# Sheet1.net
KiCad netlist of a schematic drawn in Altium Designer
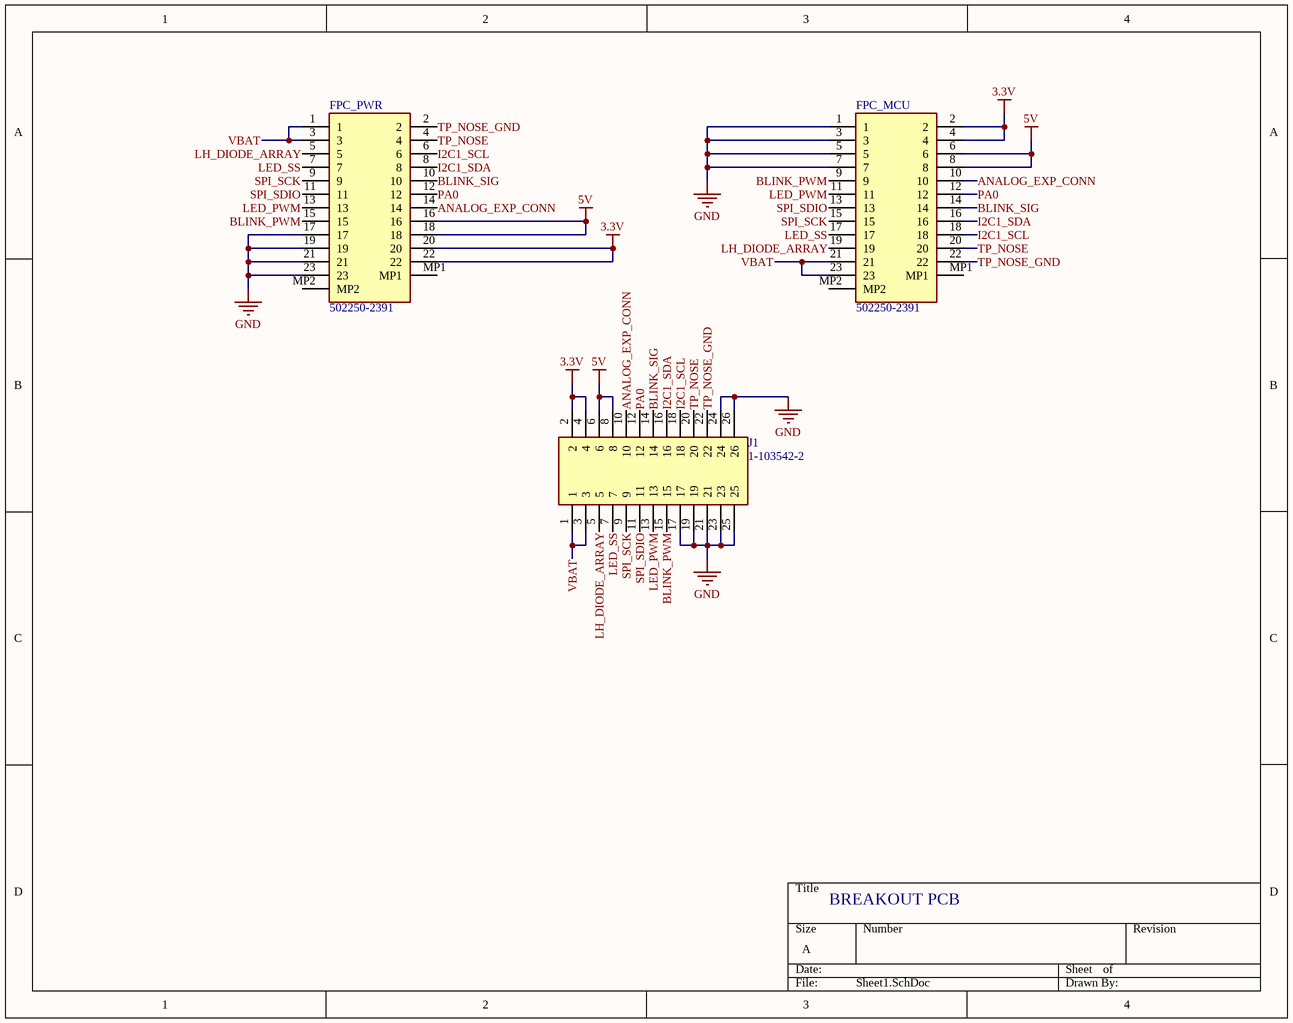
[diagram p0: Sheet1.SchDoc]

(export (version "E")
  (design (tool "Eeschema 10.0.6"))
  (components
    (comp (ref "FPC_MCU")
      (value "502250-2391")
      (footprint "SamacSys:5022502391")
      (description "Connector")
      (fields (field (name "MOUSER PART NUMBER") "538-502250-2391"))
      (libsource (lib "*") (part "502250-2391"))
    )
    (comp (ref "FPC_PWR")
      (value "502250-2391")
      (footprint "SamacSys:5022502391")
      (description "Connector")
      (fields (field (name "MOUSER PART NUMBER") "538-502250-2391"))
      (libsource (lib "*") (part "502250-2391"))
    )
    (comp (ref "J1")
      (value "1-103542-2")
      (footprint "SamacSys:HDRV26W89P254X254_2X13_3261X506X1074P")
      (description "Connector")
      (fields (field (name "MOUSER PART NUMBER") "571-1-103542-2"))
      (libsource (lib "*") (part "1-103542-2"))
    )
  )
  (nets
    (net (code "1") (name "/ANALOG_EXP_CONN") (class "Default")
      (node (ref "FPC_MCU") (pin "10") (pinfunction "10_10") (pintype "passive"))
      (node (ref "FPC_PWR") (pin "14") (pinfunction "14_14") (pintype "passive"))
      (node (ref "J1") (pin "10") (pinfunction "10_10") (pintype "passive"))
    )
    (net (code "2") (name "/BLINK_PWM") (class "Default")
      (node (ref "FPC_MCU") (pin "9") (pinfunction "9_9") (pintype "passive"))
      (node (ref "FPC_PWR") (pin "15") (pinfunction "15_15") (pintype "passive"))
      (node (ref "J1") (pin "15") (pinfunction "15_15") (pintype "passive"))
    )
    (net (code "3") (name "/BLINK_SIG") (class "Default")
      (node (ref "FPC_MCU") (pin "14") (pinfunction "14_14") (pintype "passive"))
      (node (ref "FPC_PWR") (pin "10") (pinfunction "10_10") (pintype "passive"))
      (node (ref "J1") (pin "14") (pinfunction "14_14") (pintype "passive"))
    )
    (net (code "4") (name "/I2C1_SCL") (class "Default")
      (node (ref "FPC_MCU") (pin "18") (pinfunction "18_18") (pintype "passive"))
      (node (ref "FPC_PWR") (pin "6") (pinfunction "6_6") (pintype "passive"))
      (node (ref "J1") (pin "18") (pinfunction "18_18") (pintype "passive"))
    )
    (net (code "5") (name "/I2C1_SDA") (class "Default")
      (node (ref "FPC_MCU") (pin "16") (pinfunction "16_16") (pintype "passive"))
      (node (ref "FPC_PWR") (pin "8") (pinfunction "8_8") (pintype "passive"))
      (node (ref "J1") (pin "16") (pinfunction "16_16") (pintype "passive"))
    )
    (net (code "6") (name "/LED_PWM") (class "Default")
      (node (ref "FPC_MCU") (pin "11") (pinfunction "11_11") (pintype "passive"))
      (node (ref "FPC_PWR") (pin "13") (pinfunction "13_13") (pintype "passive"))
      (node (ref "J1") (pin "13") (pinfunction "13_13") (pintype "passive"))
    )
    (net (code "7") (name "/LED_SS") (class "Default")
      (node (ref "FPC_MCU") (pin "17") (pinfunction "17_17") (pintype "passive"))
      (node (ref "FPC_PWR") (pin "7") (pinfunction "7_7") (pintype "passive"))
      (node (ref "J1") (pin "7") (pinfunction "7_7") (pintype "passive"))
    )
    (net (code "8") (name "/LH_DIODE_ARRAY") (class "Default")
      (node (ref "FPC_MCU") (pin "19") (pinfunction "19_19") (pintype "passive"))
      (node (ref "FPC_PWR") (pin "5") (pinfunction "5_5") (pintype "passive"))
      (node (ref "J1") (pin "5") (pinfunction "5_5") (pintype "passive"))
    )
    (net (code "9") (name "/PA0") (class "Default")
      (node (ref "FPC_MCU") (pin "12") (pinfunction "12_12") (pintype "passive"))
      (node (ref "FPC_PWR") (pin "12") (pinfunction "12_12") (pintype "passive"))
      (node (ref "J1") (pin "12") (pinfunction "12_12") (pintype "passive"))
    )
    (net (code "10") (name "/SPI_SCK") (class "Default")
      (node (ref "FPC_MCU") (pin "15") (pinfunction "15_15") (pintype "passive"))
      (node (ref "FPC_PWR") (pin "9") (pinfunction "9_9") (pintype "passive"))
      (node (ref "J1") (pin "9") (pinfunction "9_9") (pintype "passive"))
    )
    (net (code "11") (name "/SPI_SDIO") (class "Default")
      (node (ref "FPC_MCU") (pin "13") (pinfunction "13_13") (pintype "passive"))
      (node (ref "FPC_PWR") (pin "11") (pinfunction "11_11") (pintype "passive"))
      (node (ref "J1") (pin "11") (pinfunction "11_11") (pintype "passive"))
    )
    (net (code "12") (name "/TP_NOSE") (class "Default")
      (node (ref "FPC_MCU") (pin "20") (pinfunction "20_20") (pintype "passive"))
      (node (ref "FPC_PWR") (pin "4") (pinfunction "4_4") (pintype "passive"))
      (node (ref "J1") (pin "20") (pinfunction "20_20") (pintype "passive"))
    )
    (net (code "13") (name "/TP_NOSE_GND") (class "Default")
      (node (ref "FPC_MCU") (pin "22") (pinfunction "22_22") (pintype "passive"))
      (node (ref "FPC_PWR") (pin "2") (pinfunction "2_2") (pintype "passive"))
      (node (ref "J1") (pin "22") (pinfunction "22_22") (pintype "passive"))
    )
    (net (code "14") (name "/VBAT") (class "Default")
      (node (ref "FPC_MCU") (pin "21") (pinfunction "21_21") (pintype "passive"))
      (node (ref "FPC_MCU") (pin "23") (pinfunction "23_23") (pintype "passive"))
      (node (ref "FPC_PWR") (pin "1") (pinfunction "1_1") (pintype "passive"))
      (node (ref "FPC_PWR") (pin "3") (pinfunction "3_3") (pintype "passive"))
      (node (ref "J1") (pin "1") (pinfunction "1_1") (pintype "passive"))
      (node (ref "J1") (pin "3") (pinfunction "3_3") (pintype "passive"))
    )
    (net (code "15") (name "3.3V") (class "Default")
      (node (ref "FPC_MCU") (pin "2") (pinfunction "2_2") (pintype "passive"))
      (node (ref "FPC_MCU") (pin "4") (pinfunction "4_4") (pintype "passive"))
      (node (ref "FPC_PWR") (pin "20") (pinfunction "20_20") (pintype "passive"))
      (node (ref "FPC_PWR") (pin "22") (pinfunction "22_22") (pintype "passive"))
      (node (ref "J1") (pin "2") (pinfunction "2_2") (pintype "passive"))
      (node (ref "J1") (pin "4") (pinfunction "4_4") (pintype "passive"))
    )
    (net (code "16") (name "5V") (class "Default")
      (node (ref "FPC_MCU") (pin "6") (pinfunction "6_6") (pintype "passive"))
      (node (ref "FPC_MCU") (pin "8") (pinfunction "8_8") (pintype "passive"))
      (node (ref "FPC_PWR") (pin "16") (pinfunction "16_16") (pintype "passive"))
      (node (ref "FPC_PWR") (pin "18") (pinfunction "18_18") (pintype "passive"))
      (node (ref "J1") (pin "6") (pinfunction "6_6") (pintype "passive"))
      (node (ref "J1") (pin "8") (pinfunction "8_8") (pintype "passive"))
    )
    (net (code "17") (name "GND") (class "Default")
      (node (ref "FPC_MCU") (pin "1") (pinfunction "1_1") (pintype "passive"))
      (node (ref "FPC_MCU") (pin "3") (pinfunction "3_3") (pintype "passive"))
      (node (ref "FPC_MCU") (pin "5") (pinfunction "5_5") (pintype "passive"))
      (node (ref "FPC_MCU") (pin "7") (pinfunction "7_7") (pintype "passive"))
      (node (ref "FPC_PWR") (pin "17") (pinfunction "17_17") (pintype "passive"))
      (node (ref "FPC_PWR") (pin "19") (pinfunction "19_19") (pintype "passive"))
      (node (ref "FPC_PWR") (pin "21") (pinfunction "21_21") (pintype "passive"))
      (node (ref "FPC_PWR") (pin "23") (pinfunction "23_23") (pintype "passive"))
      (node (ref "J1") (pin "17") (pinfunction "17_17") (pintype "passive"))
      (node (ref "J1") (pin "19") (pinfunction "19_19") (pintype "passive"))
      (node (ref "J1") (pin "21") (pinfunction "21_21") (pintype "passive"))
      (node (ref "J1") (pin "23") (pinfunction "23_23") (pintype "passive"))
      (node (ref "J1") (pin "24") (pinfunction "24_24") (pintype "passive"))
      (node (ref "J1") (pin "25") (pinfunction "25_25") (pintype "passive"))
      (node (ref "J1") (pin "26") (pinfunction "26_26") (pintype "passive"))
    )
    (net (code "18") (name "unconnected-(FPC_MCU-PadMP1)") (class "Default")
      (node (ref "FPC_MCU") (pin "MP1") (pinfunction "MP1_MP1") (pintype "passive"))
    )
    (net (code "19") (name "unconnected-(FPC_MCU-PadMP2)") (class "Default")
      (node (ref "FPC_MCU") (pin "MP2") (pinfunction "MP2_MP2") (pintype "passive"))
    )
    (net (code "20") (name "unconnected-(FPC_PWR-PadMP1)") (class "Default")
      (node (ref "FPC_PWR") (pin "MP1") (pinfunction "MP1_MP1") (pintype "passive"))
    )
    (net (code "21") (name "unconnected-(FPC_PWR-PadMP2)") (class "Default")
      (node (ref "FPC_PWR") (pin "MP2") (pinfunction "MP2_MP2") (pintype "passive"))
    )
  )
)
